# invader_coin2.net
KiCad netlist of a schematic drawn in EAGLE
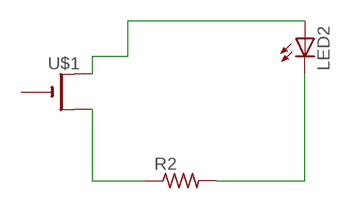
[diagram p0: schematic, sheet 1]

(export (version "E")
  (design (tool "Eeschema 10.0.6"))
  (components
    (comp (ref "LED2")
      (value "LED5MM")
      (footprint "eagle-import:LED5MM")
      (libsource (lib "eagle-import") (part "LED5MM"))
    )
    (comp (ref "R2")
      (value "R-US_0309/12")
      (footprint "eagle-import:0309_12")
      (libsource (lib "eagle-import") (part "R-US_0309/12"))
    )
    (comp (ref "U$1")
      (value "CR2032THM")
      (footprint "eagle-import:CR2032-THRU")
      (libsource (lib "eagle-import") (part "CR2032THM"))
    )
  )
  (nets
    (net (code "1") (name "Net-(LED2-C)") (class "Default")
      (node (ref "LED2") (pin "K") (pinfunction "C_K") (pintype "passive"))
      (node (ref "R2") (pin "2") (pinfunction "2_2") (pintype "passive"))
    )
    (net (code "2") (name "Net-(U$1-+)") (class "Default")
      (node (ref "LED2") (pin "A") (pinfunction "A_A") (pintype "passive"))
      (node (ref "U$1") (pin "+1") (pinfunction "+_+1") (pintype "passive"))
    )
    (net (code "3") (name "Net-(U$1-+1)") (class "Default")
      (node (ref "R2") (pin "1") (pinfunction "1_1") (pintype "passive"))
      (node (ref "U$1") (pin "+2") (pinfunction "+1_+2") (pintype "passive"))
    )
    (net (code "4") (name "unconnected-(U$1-Pad-)") (class "Default")
      (node (ref "U$1") (pin "-") (pinfunction "-_-") (pintype "passive"))
    )
  )
)
